# G1-CM4.net
KiCad netlist of a schematic drawn in Altium Designer
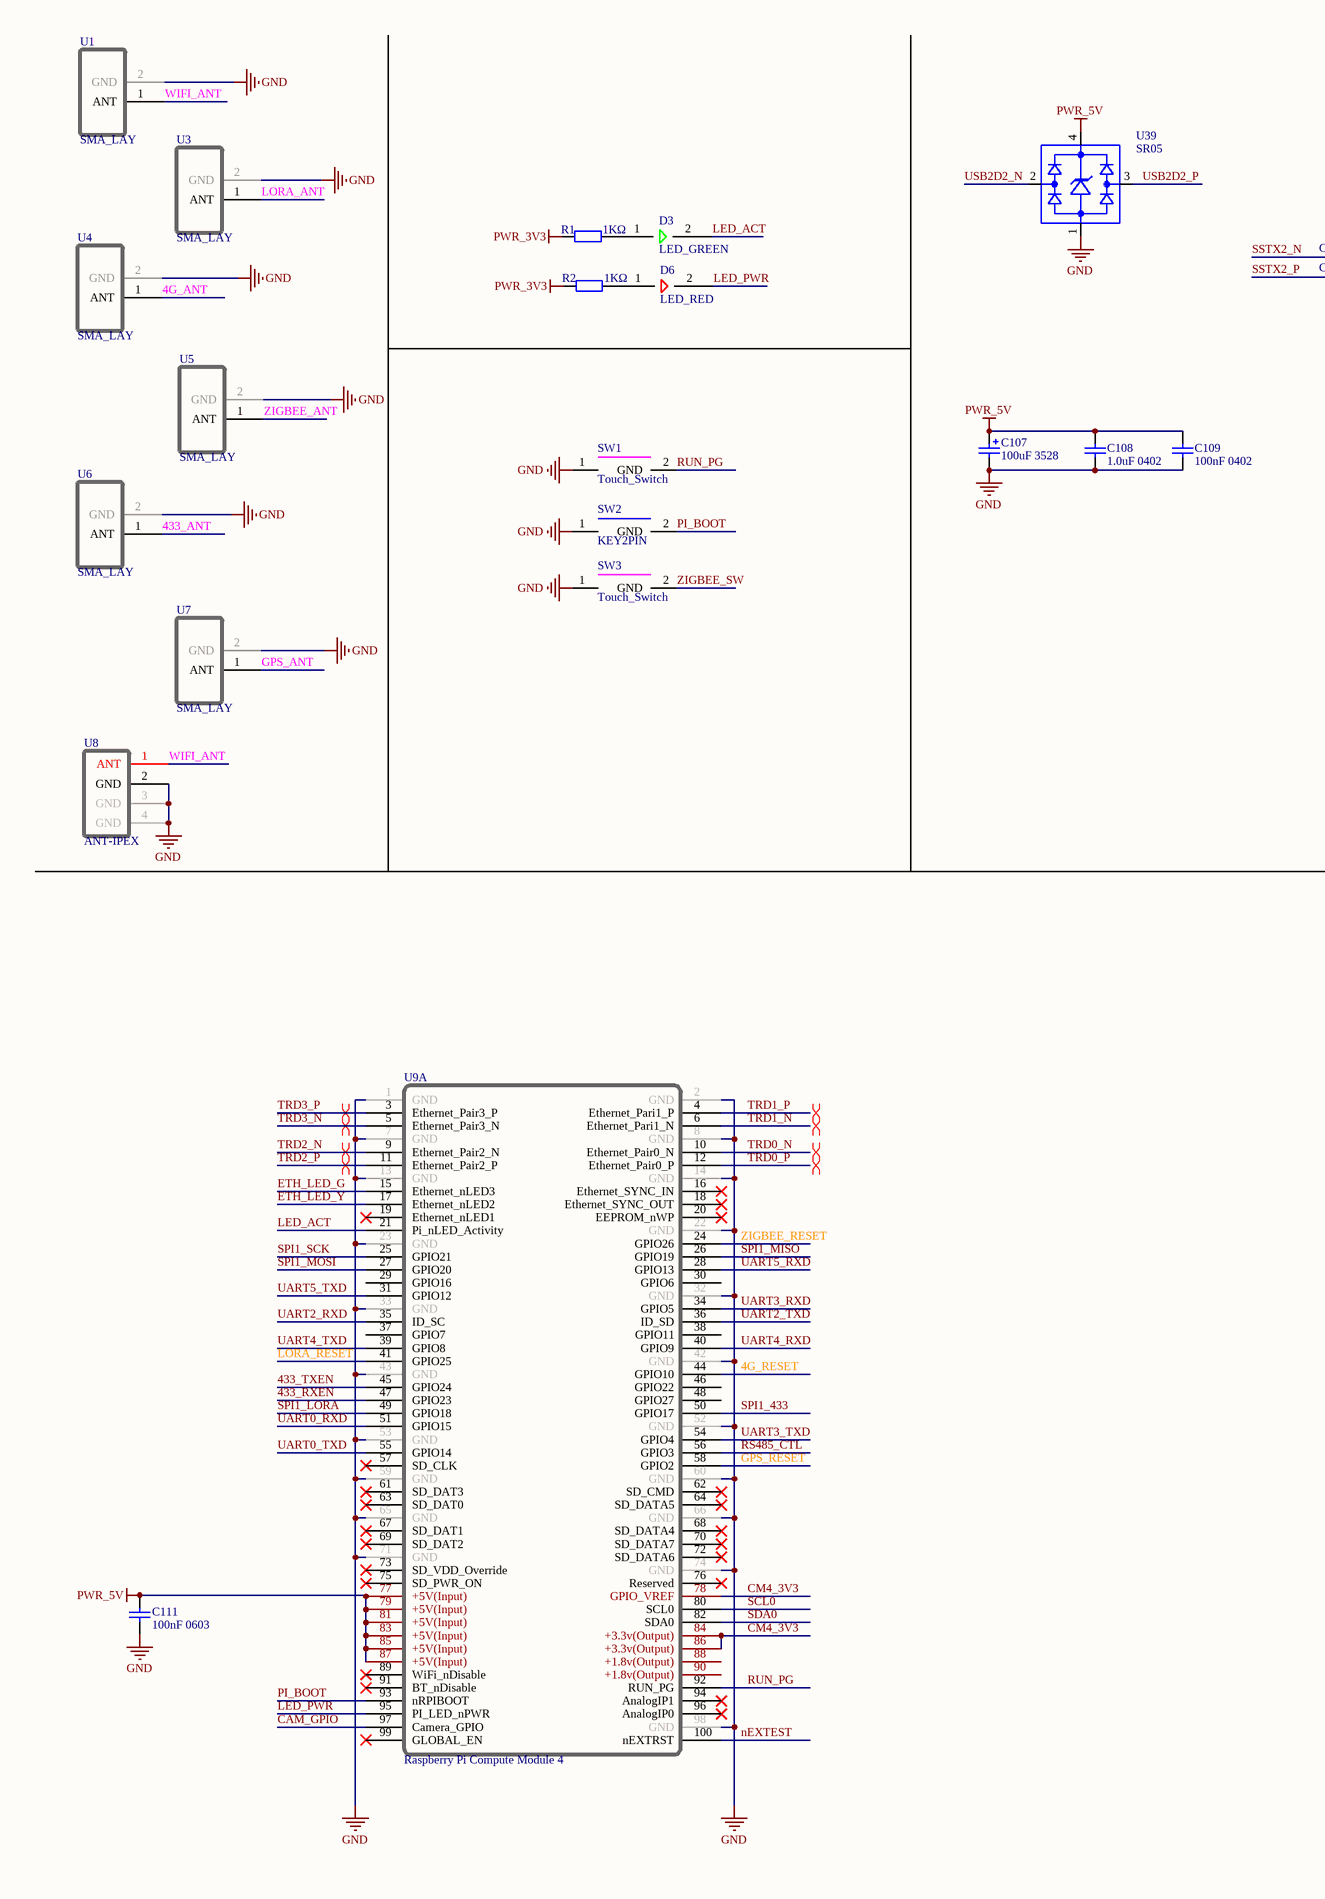
[diagram p0: G1-CM4.SchDoc, left]
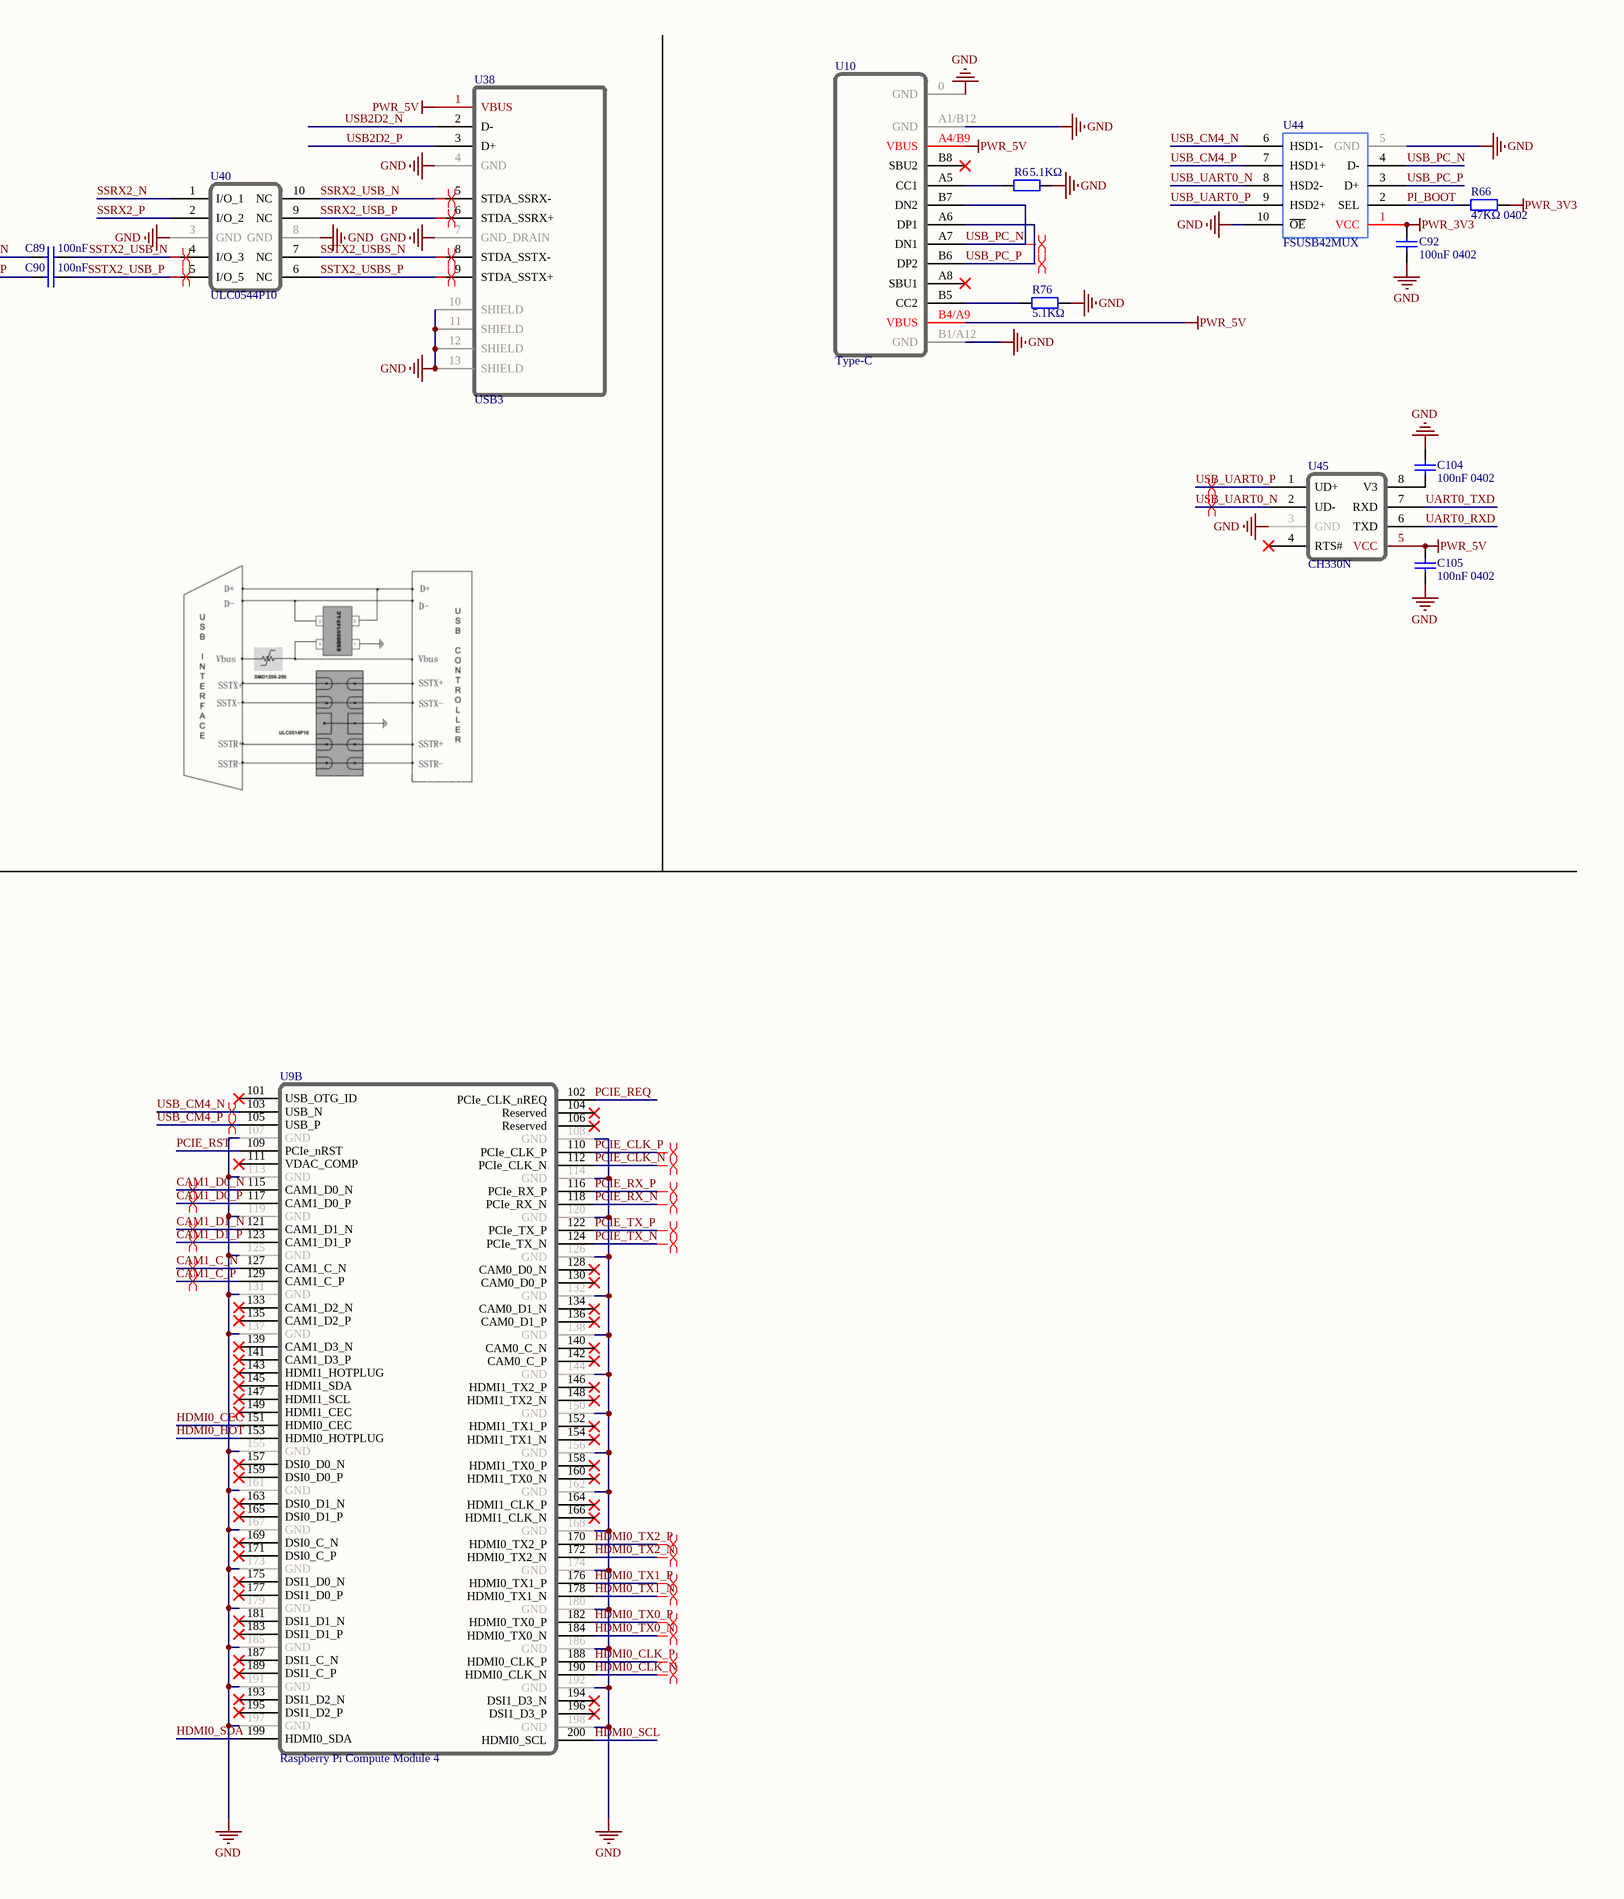
[diagram p1: G1-CM4.SchDoc, right]

(export (version "E")
  (design (tool "Eeschema 10.0.6"))
  (components
    (comp (ref "C89")
      (value "100nF")
      (footprint "0402_C")
      (description "贴片电容")
      (libsource (lib "Miscellaneous Devices LC") (part "0402 100nF (104) 10% 16V"))
    )
    (comp (ref "C90")
      (value "100nF")
      (footprint "0402_C")
      (description "贴片电容")
      (libsource (lib "Miscellaneous Devices LC") (part "0402 100nF (104) 10% 16V"))
    )
    (comp (ref "C92")
      (value "100nF 0402")
      (footprint "0402_C")
      (description "贴片电容")
      (libsource (lib "Miscellaneous Devices LC") (part "0402 100nF (104) 10% 16V"))
    )
    (comp (ref "C104")
      (value "100nF 0402")
      (footprint "0402_C")
      (description "贴片电容")
      (libsource (lib "Miscellaneous Devices LC") (part "0402 100nF (104) 10% 16V"))
    )
    (comp (ref "C105")
      (value "100nF 0402")
      (footprint "0402_C")
      (description "贴片电容")
      (libsource (lib "Miscellaneous Devices LC") (part "0402 100nF (104) 10% 16V"))
    )
    (comp (ref "C107")
      (value "100uF 3528")
      (footprint "CASE-B_3528")
      (description "钽电容")
      (libsource (lib "Miscellaneous Devices LC") (part "3528 100uF (107) 10% 6.3V"))
    )
    (comp (ref "C108")
      (value "1.0uF 0402")
      (footprint "0402_C")
      (description "贴片电容")
      (libsource (lib "Miscellaneous Devices LC") (part "0402 1.0uF (105) 10% 25V"))
    )
    (comp (ref "C109")
      (value "100nF 0402")
      (footprint "0402_C")
      (description "贴片电容")
      (libsource (lib "Miscellaneous Devices LC") (part "0402 100nF (104) 10% 16V"))
    )
    (comp (ref "C111")
      (value "100nF 0603")
      (footprint "0603_C")
      (description "贴片电容")
      (libsource (lib "Miscellaneous Devices LC") (part "0603 100nF (104) 10% 50V"))
    )
    (comp (ref "D3")
      (value "LED_GREEN")
      (footprint "LED_SIDE")
      (description "LED GREEN 0603 SIDE")
      (libsource (lib "bohao") (part "LED_GREEN"))
    )
    (comp (ref "D6")
      (value "LED_RED")
      (footprint "LED_SIDE")
      (description "LED RED 0603 SIDE")
      (libsource (lib "bohao") (part "LED_RED"))
    )
    (comp (ref "R1")
      (value "1KΩ")
      (footprint "0402_R")
      (description "贴片电阻")
      (libsource (lib "Miscellaneous Devices LC") (part "0402 1KΩ (1001) 1%"))
    )
    (comp (ref "R2")
      (value "1KΩ")
      (footprint "0402_R")
      (description "贴片电阻")
      (libsource (lib "Miscellaneous Devices LC") (part "0402 1KΩ (1001) 1%"))
    )
    (comp (ref "R6")
      (value "5.1KΩ")
      (footprint "0402_R")
      (description "贴片电阻")
      (libsource (lib "Miscellaneous Devices LC") (part "0402 5.1KΩ (5101) 1%"))
    )
    (comp (ref "R66")
      (value "47KΩ 0402")
      (footprint "0402_R")
      (description "贴片电阻")
      (libsource (lib "Miscellaneous Devices LC") (part "0402 47KΩ (4702) 1%"))
    )
    (comp (ref "R76")
      (value "5.1KΩ")
      (footprint "0402_R")
      (description "贴片电阻")
      (libsource (lib "Miscellaneous Devices LC") (part "0402 5.1KΩ (5101) 1%"))
    )
    (comp (ref "SW1")
      (value "Touch_Switch")
      (footprint "Touch_Switch")
      (description "Touch_Switch 2PIN")
      (libsource (lib "bohao") (part "Touch_Switch"))
    )
    (comp (ref "SW2")
      (value "KEY2PIN")
      (footprint "KEY2PIN")
      (description "Switch Button")
      (libsource (lib "bohao") (part "KEY2PIN"))
    )
    (comp (ref "SW3")
      (value "Touch_Switch")
      (footprint "Touch_Switch")
      (description "Touch_Switch 2PIN")
      (libsource (lib "bohao") (part "Touch_Switch"))
    )
    (comp (ref "U1")
      (value "SMA_LAY")
      (footprint "SMA-LAY")
      (description "SMA ANT LAY")
      (libsource (lib "bohao") (part "SMA_LAY"))
    )
    (comp (ref "U3")
      (value "SMA_LAY")
      (footprint "SMA-LAY")
      (description "SMA ANT LAY")
      (libsource (lib "bohao") (part "SMA_LAY"))
    )
    (comp (ref "U4")
      (value "SMA_LAY")
      (footprint "SMA-LAY")
      (description "SMA ANT LAY")
      (libsource (lib "bohao") (part "SMA_LAY"))
    )
    (comp (ref "U5")
      (value "SMA_LAY")
      (footprint "SMA-LAY")
      (description "SMA ANT LAY")
      (libsource (lib "bohao") (part "SMA_LAY"))
    )
    (comp (ref "U6")
      (value "SMA_LAY")
      (footprint "SMA-LAY")
      (description "SMA ANT LAY")
      (libsource (lib "bohao") (part "SMA_LAY"))
    )
    (comp (ref "U7")
      (value "SMA_LAY")
      (footprint "SMA-LAY")
      (description "SMA ANT LAY")
      (libsource (lib "bohao") (part "SMA_LAY"))
    )
    (comp (ref "U8")
      (value "ANT-IPEX")
      (footprint "ANT-IPEX")
      (description "ANT")
      (libsource (lib "bohao") (part "ANT-IPEX"))
    )
    (comp (ref "U9")
      (value "Raspberry Pi Compute Module 4")
      (footprint "CM4T-DF40HC(3.0)-100DS")
      (libsource (lib "bohao") (part "CM4"))
    )
    (comp (ref "U10")
      (value "Type-C")
      (footprint "Type-C-16P")
      (description "Type-C-16P")
      (libsource (lib "Mars") (part "Type-C-16P"))
    )
    (comp (ref "U38")
      (value "USB3")
      (footprint "USB3")
      (description "USB3.0")
      (libsource (lib "bohao") (part "USB3"))
    )
    (comp (ref "U39") (value "SR05") (footprint "SR05") (libsource (lib "bohao") (part "SR05")))
    (comp (ref "U40")
      (value "ULC0544P10")
      (footprint "ULC0544P10")
      (description "ESD")
      (libsource (lib "bohao") (part "ULC0544P10"))
    )
    (comp (ref "U44")
      (value "FSUSB42MUX")
      (footprint "FSUSB42MUX")
      (description "USB Switch IC 1 Channel, 10-Lead MSOP")
      (libsource (lib "bohao") (part "FSUSB42MUX"))
    )
    (comp (ref "U45")
      (value "CH330N")
      (footprint "CH330N")
      (description "USB to UART")
      (libsource (lib "bohao") (part "CH330N"))
    )
  )
  (nets
    (net (code "1") (name "/4G_ANT") (class "Default")
      (node (ref "U4") (pin "1") (pinfunction "ANT_1") (pintype "passive"))
    )
    (net (code "2") (name "/4G_RESET") (class "Default")
      (node (ref "U9") (pin "44") (pinfunction "GPIO10_44") (pintype "passive"))
    )
    (net (code "3") (name "/433_ANT") (class "Default")
      (node (ref "U6") (pin "1") (pinfunction "ANT_1") (pintype "passive"))
    )
    (net (code "4") (name "/433_RXEN") (class "Default")
      (node (ref "U9") (pin "47") (pinfunction "GPIO23_47") (pintype "passive"))
    )
    (net (code "5") (name "/433_TXEN") (class "Default")
      (node (ref "U9") (pin "45") (pinfunction "GPIO24_45") (pintype "passive"))
    )
    (net (code "6") (name "/CAM1_C_N") (class "Default")
      (node (ref "U9") (pin "127") (pinfunction "CAM1_C_N_127") (pintype "passive"))
    )
    (net (code "7") (name "/CAM1_C_P") (class "Default")
      (node (ref "U9") (pin "129") (pinfunction "CAM1_C_P_129") (pintype "passive"))
    )
    (net (code "8") (name "/CAM1_D0_N") (class "Default")
      (node (ref "U9") (pin "115") (pinfunction "CAM1_D0_N_115") (pintype "passive"))
    )
    (net (code "9") (name "/CAM1_D0_P") (class "Default")
      (node (ref "U9") (pin "117") (pinfunction "CAM1_D0_P_117") (pintype "passive"))
    )
    (net (code "10") (name "/CAM1_D1_N") (class "Default")
      (node (ref "U9") (pin "121") (pinfunction "CAM1_D1_N_121") (pintype "passive"))
    )
    (net (code "11") (name "/CAM1_D1_P") (class "Default")
      (node (ref "U9") (pin "123") (pinfunction "CAM1_D1_P_123") (pintype "passive"))
    )
    (net (code "12") (name "/CAM_GPIO") (class "Default")
      (node (ref "U9") (pin "97") (pinfunction "Camera_GPIO_97") (pintype "passive"))
    )
    (net (code "13") (name "/CM4_3V3") (class "Default")
      (node (ref "U9") (pin "78") (pinfunction "GPIO_VREF_78") (pintype "passive"))
      (node (ref "U9") (pin "84") (pinfunction "+3.3v(Output)_84") (pintype "passive"))
      (node (ref "U9") (pin "86") (pinfunction "+3.3v(Output)_86") (pintype "passive"))
    )
    (net (code "14") (name "/ETH_LED_G") (class "Default")
      (node (ref "U9") (pin "15") (pinfunction "Ethernet_nLED3_15") (pintype "passive"))
    )
    (net (code "15") (name "/ETH_LED_Y") (class "Default")
      (node (ref "U9") (pin "17") (pinfunction "Ethernet_nLED2_17") (pintype "passive"))
    )
    (net (code "16") (name "/GPS_ANT") (class "Default")
      (node (ref "U7") (pin "1") (pinfunction "ANT_1") (pintype "passive"))
    )
    (net (code "17") (name "/GPS_RESET") (class "Default")
      (node (ref "U9") (pin "58") (pinfunction "GPIO2_58") (pintype "passive"))
    )
    (net (code "18") (name "/HDMI0_CEC") (class "Default")
      (node (ref "U9") (pin "151") (pinfunction "HDMI0_CEC_151") (pintype "passive"))
    )
    (net (code "19") (name "/HDMI0_CLK_N") (class "Default")
      (node (ref "U9") (pin "190") (pinfunction "HDMI0_CLK_N_190") (pintype "passive"))
    )
    (net (code "20") (name "/HDMI0_CLK_P") (class "Default")
      (node (ref "U9") (pin "188") (pinfunction "HDMI0_CLK_P_188") (pintype "passive"))
    )
    (net (code "21") (name "/HDMI0_HOT") (class "Default")
      (node (ref "U9") (pin "153") (pinfunction "HDMI0_HOTPLUG_153") (pintype "passive"))
    )
    (net (code "22") (name "/HDMI0_SCL") (class "Default")
      (node (ref "U9") (pin "200") (pinfunction "HDMI0_SCL_200") (pintype "passive"))
    )
    (net (code "23") (name "/HDMI0_SDA") (class "Default")
      (node (ref "U9") (pin "199") (pinfunction "HDMI0_SDA_199") (pintype "passive"))
    )
    (net (code "24") (name "/HDMI0_TX0_N") (class "Default")
      (node (ref "U9") (pin "184") (pinfunction "HDMI0_TX0_N_184") (pintype "passive"))
    )
    (net (code "25") (name "/HDMI0_TX0_P") (class "Default")
      (node (ref "U9") (pin "182") (pinfunction "HDMI0_TX0_P_182") (pintype "passive"))
    )
    (net (code "26") (name "/HDMI0_TX1_N") (class "Default")
      (node (ref "U9") (pin "178") (pinfunction "HDMI0_TX1_N_178") (pintype "passive"))
    )
    (net (code "27") (name "/HDMI0_TX1_P") (class "Default")
      (node (ref "U9") (pin "176") (pinfunction "HDMI0_TX1_P_176") (pintype "passive"))
    )
    (net (code "28") (name "/HDMI0_TX2_N") (class "Default")
      (node (ref "U9") (pin "172") (pinfunction "HDMI0_TX2_N_172") (pintype "passive"))
    )
    (net (code "29") (name "/HDMI0_TX2_P") (class "Default")
      (node (ref "U9") (pin "170") (pinfunction "HDMI0_TX2_P_170") (pintype "passive"))
    )
    (net (code "30") (name "/LED_ACT") (class "Default")
      (node (ref "D3") (pin "2") (pintype "passive"))
      (node (ref "U9") (pin "21") (pinfunction "Pi_nLED_Activity_21") (pintype "passive"))
    )
    (net (code "31") (name "/LED_PWR") (class "Default")
      (node (ref "D6") (pin "2") (pintype "passive"))
      (node (ref "U9") (pin "95") (pinfunction "PI_LED_nPWR_95") (pintype "passive"))
    )
    (net (code "32") (name "/LORA_ANT") (class "Default")
      (node (ref "U3") (pin "1") (pinfunction "ANT_1") (pintype "passive"))
    )
    (net (code "33") (name "/LORA_RESET") (class "Default")
      (node (ref "U9") (pin "41") (pinfunction "GPIO25_41") (pintype "passive"))
    )
    (net (code "34") (name "/PCIE_CLK_N") (class "Default")
      (node (ref "U9") (pin "112") (pinfunction "PCIe_CLK_N_112") (pintype "passive"))
    )
    (net (code "35") (name "/PCIE_CLK_P") (class "Default")
      (node (ref "U9") (pin "110") (pinfunction "PCIe_CLK_P_110") (pintype "passive"))
    )
    (net (code "36") (name "/PCIE_REQ") (class "Default")
      (node (ref "U9") (pin "102") (pinfunction "PCIe_CLK_nREQ_102") (pintype "passive"))
    )
    (net (code "37") (name "/PCIE_RST") (class "Default")
      (node (ref "U9") (pin "109") (pinfunction "PCIe_nRST_109") (pintype "passive"))
    )
    (net (code "38") (name "/PCIE_RX_N") (class "Default")
      (node (ref "U9") (pin "118") (pinfunction "PCIe_RX_N_118") (pintype "passive"))
    )
    (net (code "39") (name "/PCIE_RX_P") (class "Default")
      (node (ref "U9") (pin "116") (pinfunction "PCIe_RX_P_116") (pintype "passive"))
    )
    (net (code "40") (name "/PCIE_TX_N") (class "Default")
      (node (ref "U9") (pin "124") (pinfunction "PCIe_TX_N_124") (pintype "passive"))
    )
    (net (code "41") (name "/PCIE_TX_P") (class "Default")
      (node (ref "U9") (pin "122") (pinfunction "PCIe_TX_P_122") (pintype "passive"))
    )
    (net (code "42") (name "/PI_BOOT") (class "Default")
      (node (ref "R66") (pin "2") (pinfunction "2_2") (pintype "passive"))
      (node (ref "SW2") (pin "2") (pinfunction "GND_2") (pintype "passive"))
      (node (ref "U44") (pin "2") (pinfunction "SEL_2") (pintype "passive"))
      (node (ref "U9") (pin "93") (pinfunction "nRPIBOOT_93") (pintype "passive"))
    )
    (net (code "43") (name "/RS485_CTL") (class "Default")
      (node (ref "U9") (pin "56") (pinfunction "GPIO3_56") (pintype "passive"))
    )
    (net (code "44") (name "/RUN_PG") (class "Default")
      (node (ref "SW1") (pin "2") (pinfunction "GND_2") (pintype "passive"))
      (node (ref "U9") (pin "92") (pinfunction "RUN_PG_92") (pintype "passive"))
    )
    (net (code "45") (name "/SCL0") (class "Default")
      (node (ref "U9") (pin "80") (pinfunction "SCL0_80") (pintype "passive"))
    )
    (net (code "46") (name "/SDA0") (class "Default")
      (node (ref "U9") (pin "82") (pinfunction "SDA0_82") (pintype "passive"))
    )
    (net (code "47") (name "/SPI1_433") (class "Default")
      (node (ref "U9") (pin "50") (pinfunction "GPIO17_50") (pintype "passive"))
    )
    (net (code "48") (name "/SPI1_LORA") (class "Default")
      (node (ref "U9") (pin "49") (pinfunction "GPIO18_49") (pintype "passive"))
    )
    (net (code "49") (name "/SPI1_MISO") (class "Default")
      (node (ref "U9") (pin "26") (pinfunction "GPIO19_26") (pintype "passive"))
    )
    (net (code "50") (name "/SPI1_MOSI") (class "Default")
      (node (ref "U9") (pin "27") (pinfunction "GPIO20_27") (pintype "passive"))
    )
    (net (code "51") (name "/SPI1_SCK") (class "Default")
      (node (ref "U9") (pin "25") (pinfunction "GPIO21_25") (pintype "passive"))
    )
    (net (code "52") (name "/SSRX2_N") (class "Default")
      (node (ref "U40") (pin "1") (pinfunction "I/O_1_1") (pintype "passive"))
    )
    (net (code "53") (name "/SSRX2_P") (class "Default")
      (node (ref "U40") (pin "2") (pinfunction "I/O_2_2") (pintype "passive"))
    )
    (net (code "54") (name "/SSRX2_USB_N") (class "Default")
      (node (ref "U38") (pin "5") (pinfunction "STDA_SSRX-_5") (pintype "passive"))
      (node (ref "U40") (pin "10") (pinfunction "NC_10") (pintype "passive"))
    )
    (net (code "55") (name "/SSRX2_USB_P") (class "Default")
      (node (ref "U38") (pin "6") (pinfunction "STDA_SSRX+_6") (pintype "passive"))
      (node (ref "U40") (pin "9") (pinfunction "NC_9") (pintype "passive"))
    )
    (net (code "56") (name "/SSTX2_N") (class "Default")
      (node (ref "C89") (pin "1") (pinfunction "1_1") (pintype "passive"))
    )
    (net (code "57") (name "/SSTX2_P") (class "Default")
      (node (ref "C90") (pin "1") (pinfunction "1_1") (pintype "passive"))
    )
    (net (code "58") (name "/SSTX2_USBS_N") (class "Default")
      (node (ref "U38") (pin "8") (pinfunction "STDA_SSTX-_8") (pintype "passive"))
      (node (ref "U40") (pin "7") (pinfunction "NC_7") (pintype "passive"))
    )
    (net (code "59") (name "/SSTX2_USBS_P") (class "Default")
      (node (ref "U38") (pin "9") (pinfunction "STDA_SSTX+_9") (pintype "passive"))
      (node (ref "U40") (pin "6") (pinfunction "NC_6") (pintype "passive"))
    )
    (net (code "60") (name "/SSTX2_USB_N") (class "Default")
      (node (ref "C89") (pin "2") (pinfunction "2_2") (pintype "passive"))
      (node (ref "U40") (pin "4") (pinfunction "I/O_3_4") (pintype "passive"))
    )
    (net (code "61") (name "/SSTX2_USB_P") (class "Default")
      (node (ref "C90") (pin "2") (pinfunction "2_2") (pintype "passive"))
      (node (ref "U40") (pin "5") (pinfunction "I/O_5_5") (pintype "passive"))
    )
    (net (code "62") (name "/TRD0_N") (class "Default")
      (node (ref "U9") (pin "10") (pinfunction "Ethernet_Pair0_N_10") (pintype "passive"))
    )
    (net (code "63") (name "/TRD0_P") (class "Default")
      (node (ref "U9") (pin "12") (pinfunction "Ethernet_Pair0_P_12") (pintype "passive"))
    )
    (net (code "64") (name "/TRD1_N") (class "Default")
      (node (ref "U9") (pin "6") (pinfunction "Ethernet_Pari1_N_6") (pintype "passive"))
    )
    (net (code "65") (name "/TRD1_P") (class "Default")
      (node (ref "U9") (pin "4") (pinfunction "Ethernet_Pari1_P_4") (pintype "passive"))
    )
    (net (code "66") (name "/TRD2_N") (class "Default")
      (node (ref "U9") (pin "9") (pinfunction "Ethernet_Pair2_N_9") (pintype "passive"))
    )
    (net (code "67") (name "/TRD2_P") (class "Default")
      (node (ref "U9") (pin "11") (pinfunction "Ethernet_Pair2_P_11") (pintype "passive"))
    )
    (net (code "68") (name "/TRD3_N") (class "Default")
      (node (ref "U9") (pin "5") (pinfunction "Ethernet_Pair3_N_5") (pintype "passive"))
    )
    (net (code "69") (name "/TRD3_P") (class "Default")
      (node (ref "U9") (pin "3") (pinfunction "Ethernet_Pair3_P_3") (pintype "passive"))
    )
    (net (code "70") (name "/UART0_RXD") (class "Default")
      (node (ref "U45") (pin "6") (pinfunction "TXD_6") (pintype "passive"))
      (node (ref "U9") (pin "51") (pinfunction "GPIO15_51") (pintype "passive"))
    )
    (net (code "71") (name "/UART0_TXD") (class "Default")
      (node (ref "U45") (pin "7") (pinfunction "RXD_7") (pintype "passive"))
      (node (ref "U9") (pin "55") (pinfunction "GPIO14_55") (pintype "passive"))
    )
    (net (code "72") (name "/UART2_RXD") (class "Default")
      (node (ref "U9") (pin "35") (pinfunction "ID_SC_35") (pintype "passive"))
    )
    (net (code "73") (name "/UART2_TXD") (class "Default")
      (node (ref "U9") (pin "36") (pinfunction "ID_SD_36") (pintype "passive"))
    )
    (net (code "74") (name "/UART3_RXD") (class "Default")
      (node (ref "U9") (pin "34") (pinfunction "GPIO5_34") (pintype "passive"))
    )
    (net (code "75") (name "/UART3_TXD") (class "Default")
      (node (ref "U9") (pin "54") (pinfunction "GPIO4_54") (pintype "passive"))
    )
    (net (code "76") (name "/UART4_RXD") (class "Default")
      (node (ref "U9") (pin "40") (pinfunction "GPIO9_40") (pintype "passive"))
    )
    (net (code "77") (name "/UART4_TXD") (class "Default")
      (node (ref "U9") (pin "39") (pinfunction "GPIO8_39") (pintype "passive"))
    )
    (net (code "78") (name "/UART5_RXD") (class "Default")
      (node (ref "U9") (pin "28") (pinfunction "GPIO13_28") (pintype "passive"))
    )
    (net (code "79") (name "/UART5_TXD") (class "Default")
      (node (ref "U9") (pin "31") (pinfunction "GPIO12_31") (pintype "passive"))
    )
    (net (code "80") (name "/USB2D2_N") (class "Default")
      (node (ref "U38") (pin "2") (pinfunction "D-_2") (pintype "passive"))
      (node (ref "U39") (pin "2") (pinfunction "2_2") (pintype "passive"))
    )
    (net (code "81") (name "/USB2D2_P") (class "Default")
      (node (ref "U38") (pin "3") (pinfunction "D+_3") (pintype "passive"))
      (node (ref "U39") (pin "3") (pinfunction "3_3") (pintype "passive"))
    )
    (net (code "82") (name "/USB_CM4_N") (class "Default")
      (node (ref "U44") (pin "6") (pinfunction "HSD1-_6") (pintype "passive"))
      (node (ref "U9") (pin "103") (pinfunction "USB_N_103") (pintype "passive"))
    )
    (net (code "83") (name "/USB_CM4_P") (class "Default")
      (node (ref "U44") (pin "7") (pinfunction "HSD1+_7") (pintype "passive"))
      (node (ref "U9") (pin "105") (pinfunction "USB_P_105") (pintype "passive"))
    )
    (net (code "84") (name "/USB_PC_N") (class "Default")
      (node (ref "U10") (pin "A7") (pinfunction "DN1_A7") (pintype "passive"))
      (node (ref "U10") (pin "B7") (pinfunction "DN2_B7") (pintype "passive"))
      (node (ref "U44") (pin "4") (pinfunction "D-_4") (pintype "passive"))
    )
    (net (code "85") (name "/USB_PC_P") (class "Default")
      (node (ref "U10") (pin "A6") (pinfunction "DP1_A6") (pintype "passive"))
      (node (ref "U10") (pin "B6") (pinfunction "DP2_B6") (pintype "passive"))
      (node (ref "U44") (pin "3") (pinfunction "D+_3") (pintype "passive"))
    )
    (net (code "86") (name "/USB_UART0_N") (class "Default")
      (node (ref "U44") (pin "8") (pinfunction "HSD2-_8") (pintype "passive"))
      (node (ref "U45") (pin "2") (pinfunction "UD-_2") (pintype "passive"))
    )
    (net (code "87") (name "/USB_UART0_P") (class "Default")
      (node (ref "U44") (pin "9") (pinfunction "HSD2+_9") (pintype "passive"))
      (node (ref "U45") (pin "1") (pinfunction "UD+_1") (pintype "passive"))
    )
    (net (code "88") (name "/WIFI_ANT") (class "Default")
      (node (ref "U1") (pin "1") (pinfunction "ANT_1") (pintype "passive"))
      (node (ref "U8") (pin "1") (pinfunction "ANT_1") (pintype "passive"))
    )
    (net (code "89") (name "/ZIGBEE_ANT") (class "Default")
      (node (ref "U5") (pin "1") (pinfunction "ANT_1") (pintype "passive"))
    )
    (net (code "90") (name "/ZIGBEE_RESET") (class "Default")
      (node (ref "U9") (pin "24") (pinfunction "GPIO26_24") (pintype "passive"))
    )
    (net (code "91") (name "/ZIGBEE_SW") (class "Default")
      (node (ref "SW3") (pin "2") (pinfunction "GND_2") (pintype "passive"))
    )
    (net (code "92") (name "/nEXTEST") (class "Default")
      (node (ref "U9") (pin "100") (pinfunction "nEXTRST_100") (pintype "passive"))
    )
    (net (code "93") (name "GND") (class "Default")
      (node (ref "C104") (pin "2") (pinfunction "2_2") (pintype "passive"))
      (node (ref "C105") (pin "1") (pinfunction "1_1") (pintype "passive"))
      (node (ref "C107") (pin "2") (pinfunction "2_2") (pintype "passive"))
      (node (ref "C108") (pin "1") (pinfunction "1_1") (pintype "passive"))
      (node (ref "C109") (pin "1") (pinfunction "1_1") (pintype "passive"))
      (node (ref "C111") (pin "1") (pinfunction "1_1") (pintype "passive"))
      (node (ref "C92") (pin "1") (pinfunction "1_1") (pintype "passive"))
      (node (ref "R6") (pin "2") (pinfunction "2_2") (pintype "passive"))
      (node (ref "R76") (pin "2") (pinfunction "2_2") (pintype "passive"))
      (node (ref "SW1") (pin "1") (pinfunction "1_1") (pintype "passive"))
      (node (ref "SW2") (pin "1") (pinfunction "1_1") (pintype "passive"))
      (node (ref "SW3") (pin "1") (pinfunction "1_1") (pintype "passive"))
      (node (ref "U1") (pin "2") (pinfunction "GND_2") (pintype "passive"))
      (node (ref "U10") (pin "0") (pinfunction "GND_0") (pintype "passive"))
      (node (ref "U10") (pin "A1/B12") (pinfunction "GND_A1/B12") (pintype "passive"))
      (node (ref "U10") (pin "B1/A12") (pinfunction "GND_B1/A12") (pintype "passive"))
      (node (ref "U3") (pin "2") (pinfunction "GND_2") (pintype "passive"))
      (node (ref "U38") (pin "10") (pinfunction "SHIELD_10") (pintype "passive"))
      (node (ref "U38") (pin "11") (pinfunction "SHIELD_11") (pintype "passive"))
      (node (ref "U38") (pin "12") (pinfunction "SHIELD_12") (pintype "passive"))
      (node (ref "U38") (pin "13") (pinfunction "SHIELD_13") (pintype "passive"))
      (node (ref "U38") (pin "4") (pinfunction "GND_4") (pintype "passive"))
      (node (ref "U38") (pin "7") (pinfunction "GND_DRAIN_7") (pintype "passive"))
      (node (ref "U39") (pin "1") (pinfunction "1_1") (pintype "passive"))
      (node (ref "U4") (pin "2") (pinfunction "GND_2") (pintype "passive"))
      (node (ref "U40") (pin "3") (pinfunction "GND_3") (pintype "passive"))
      (node (ref "U40") (pin "8") (pinfunction "GND_8") (pintype "passive"))
      (node (ref "U44") (pin "10") (pinfunction "~{OE}_10") (pintype "passive"))
      (node (ref "U44") (pin "5") (pinfunction "GND_5") (pintype "passive"))
      (node (ref "U45") (pin "3") (pinfunction "GND_3") (pintype "passive"))
      (node (ref "U5") (pin "2") (pinfunction "GND_2") (pintype "passive"))
      (node (ref "U6") (pin "2") (pinfunction "GND_2") (pintype "passive"))
      (node (ref "U7") (pin "2") (pinfunction "GND_2") (pintype "passive"))
      (node (ref "U8") (pin "2") (pinfunction "GND_2") (pintype "passive"))
      (node (ref "U8") (pin "3") (pinfunction "GND_3") (pintype "passive"))
      (node (ref "U8") (pin "4") (pinfunction "GND_4") (pintype "passive"))
      (node (ref "U9") (pin "1") (pinfunction "GND_1") (pintype "passive"))
      (node (ref "U9") (pin "107") (pinfunction "GND_107") (pintype "passive"))
      (node (ref "U9") (pin "108") (pinfunction "GND_108") (pintype "passive"))
      (node (ref "U9") (pin "113") (pinfunction "GND_113") (pintype "passive"))
      (node (ref "U9") (pin "114") (pinfunction "GND_114") (pintype "passive"))
      (node (ref "U9") (pin "119") (pinfunction "GND_119") (pintype "passive"))
      (node (ref "U9") (pin "120") (pinfunction "GND_120") (pintype "passive"))
      (node (ref "U9") (pin "125") (pinfunction "GND_125") (pintype "passive"))
      (node (ref "U9") (pin "126") (pinfunction "GND_126") (pintype "passive"))
      (node (ref "U9") (pin "13") (pinfunction "GND_13") (pintype "passive"))
      (node (ref "U9") (pin "131") (pinfunction "GND_131") (pintype "passive"))
      (node (ref "U9") (pin "132") (pinfunction "GND_132") (pintype "passive"))
      (node (ref "U9") (pin "137") (pinfunction "GND_137") (pintype "passive"))
      (node (ref "U9") (pin "138") (pinfunction "GND_138") (pintype "passive"))
      (node (ref "U9") (pin "14") (pinfunction "GND_14") (pintype "passive"))
      (node (ref "U9") (pin "144") (pinfunction "GND_144") (pintype "passive"))
      (node (ref "U9") (pin "150") (pinfunction "GND_150") (pintype "passive"))
      (node (ref "U9") (pin "155") (pinfunction "GND_155") (pintype "passive"))
      (node (ref "U9") (pin "156") (pinfunction "GND_156") (pintype "passive"))
      (node (ref "U9") (pin "161") (pinfunction "GND_161") (pintype "passive"))
      (node (ref "U9") (pin "162") (pinfunction "GND_162") (pintype "passive"))
      (node (ref "U9") (pin "167") (pinfunction "GND_167") (pintype "passive"))
      (node (ref "U9") (pin "168") (pinfunction "GND_168") (pintype "passive"))
      (node (ref "U9") (pin "173") (pinfunction "GND_173") (pintype "passive"))
      (node (ref "U9") (pin "174") (pinfunction "GND_174") (pintype "passive"))
      (node (ref "U9") (pin "179") (pinfunction "GND_179") (pintype "passive"))
      (node (ref "U9") (pin "180") (pinfunction "GND_180") (pintype "passive"))
      (node (ref "U9") (pin "185") (pinfunction "GND_185") (pintype "passive"))
      (node (ref "U9") (pin "186") (pinfunction "GND_186") (pintype "passive"))
      (node (ref "U9") (pin "191") (pinfunction "GND_191") (pintype "passive"))
      (node (ref "U9") (pin "192") (pinfunction "GND_192") (pintype "passive"))
      (node (ref "U9") (pin "197") (pinfunction "GND_197") (pintype "passive"))
      (node (ref "U9") (pin "198") (pinfunction "GND_198") (pintype "passive"))
      (node (ref "U9") (pin "2") (pinfunction "GND_2") (pintype "passive"))
      (node (ref "U9") (pin "22") (pinfunction "GND_22") (pintype "passive"))
      (node (ref "U9") (pin "23") (pinfunction "GND_23") (pintype "passive"))
      (node (ref "U9") (pin "32") (pinfunction "GND_32") (pintype "passive"))
      (node (ref "U9") (pin "33") (pinfunction "GND_33") (pintype "passive"))
      (node (ref "U9") (pin "42") (pinfunction "GND_42") (pintype "passive"))
      (node (ref "U9") (pin "43") (pinfunction "GND_43") (pintype "passive"))
      (node (ref "U9") (pin "52") (pinfunction "GND_52") (pintype "passive"))
      (node (ref "U9") (pin "53") (pinfunction "GND_53") (pintype "passive"))
      (node (ref "U9") (pin "59") (pinfunction "GND_59") (pintype "passive"))
      (node (ref "U9") (pin "60") (pinfunction "GND_60") (pintype "passive"))
      (node (ref "U9") (pin "65") (pinfunction "GND_65") (pintype "passive"))
      (node (ref "U9") (pin "66") (pinfunction "GND_66") (pintype "passive"))
      (node (ref "U9") (pin "7") (pinfunction "GND_7") (pintype "passive"))
      (node (ref "U9") (pin "71") (pinfunction "GND_71") (pintype "passive"))
      (node (ref "U9") (pin "74") (pinfunction "GND_74") (pintype "passive"))
      (node (ref "U9") (pin "8") (pinfunction "GND_8") (pintype "passive"))
      (node (ref "U9") (pin "98") (pinfunction "GND_98") (pintype "passive"))
    )
    (net (code "94") (name "Net-(D3-Pad1)") (class "Default")
      (node (ref "D3") (pin "1") (pintype "passive"))
      (node (ref "R1") (pin "2") (pinfunction "2_2") (pintype "passive"))
    )
    (net (code "95") (name "Net-(D6-Pad1)") (class "Default")
      (node (ref "D6") (pin "1") (pintype "passive"))
      (node (ref "R2") (pin "2") (pinfunction "2_2") (pintype "passive"))
    )
    (net (code "96") (name "Net-(U10-CC1)") (class "Default")
      (node (ref "R6") (pin "1") (pinfunction "1_1") (pintype "passive"))
      (node (ref "U10") (pin "A5") (pinfunction "CC1_A5") (pintype "passive"))
    )
    (net (code "97") (name "Net-(U10-CC2)") (class "Default")
      (node (ref "R76") (pin "1") (pinfunction "1_1") (pintype "passive"))
      (node (ref "U10") (pin "B5") (pinfunction "CC2_B5") (pintype "passive"))
    )
    (net (code "98") (name "Net-(U45-V3)") (class "Default")
      (node (ref "C104") (pin "1") (pinfunction "1_1") (pintype "passive"))
      (node (ref "U45") (pin "8") (pinfunction "V3_8") (pintype "passive"))
    )
    (net (code "99") (name "PWR_3V3") (class "Default")
      (node (ref "C92") (pin "2") (pinfunction "2_2") (pintype "passive"))
      (node (ref "R1") (pin "1") (pinfunction "1_1") (pintype "passive"))
      (node (ref "R2") (pin "1") (pinfunction "1_1") (pintype "passive"))
      (node (ref "R66") (pin "1") (pinfunction "1_1") (pintype "passive"))
      (node (ref "U44") (pin "1") (pinfunction "VCC_1") (pintype "passive"))
    )
    (net (code "100") (name "PWR_5V") (class "Default")
      (node (ref "C105") (pin "2") (pinfunction "2_2") (pintype "passive"))
      (node (ref "C107") (pin "1") (pinfunction "1_1") (pintype "passive"))
      (node (ref "C108") (pin "2") (pinfunction "2_2") (pintype "passive"))
      (node (ref "C109") (pin "2") (pinfunction "2_2") (pintype "passive"))
      (node (ref "C111") (pin "2") (pinfunction "2_2") (pintype "passive"))
      (node (ref "U10") (pin "A4/B9") (pinfunction "VBUS_A4/B9") (pintype "passive"))
      (node (ref "U10") (pin "B4/A9") (pinfunction "VBUS_B4/A9") (pintype "passive"))
      (node (ref "U38") (pin "1") (pinfunction "VBUS_1") (pintype "power_in"))
      (node (ref "U39") (pin "4") (pinfunction "4_4") (pintype "passive"))
      (node (ref "U45") (pin "5") (pinfunction "VCC_5") (pintype "passive"))
      (node (ref "U9") (pin "77") (pinfunction "+5V(Input)_77") (pintype "passive"))
      (node (ref "U9") (pin "79") (pinfunction "+5V(Input)_79") (pintype "passive"))
      (node (ref "U9") (pin "81") (pinfunction "+5V(Input)_81") (pintype "passive"))
      (node (ref "U9") (pin "83") (pinfunction "+5V(Input)_83") (pintype "passive"))
      (node (ref "U9") (pin "85") (pinfunction "+5V(Input)_85") (pintype "passive"))
      (node (ref "U9") (pin "87") (pinfunction "+5V(Input)_87") (pintype "passive"))
    )
    (net (code "101") (name "unconnected-(U9A-+1.8v(Output)-Pad88)") (class "Default")
      (node (ref "U9") (pin "88") (pinfunction "+1.8v(Output)_88") (pintype "passive"))
    )
    (net (code "102") (name "unconnected-(U9A-+1.8v(Output)-Pad90)") (class "Default")
      (node (ref "U9") (pin "90") (pinfunction "+1.8v(Output)_90") (pintype "passive"))
    )
    (net (code "103") (name "unconnected-(U9A-AnalogIP0-Pad96)") (class "Default")
      (node (ref "U9") (pin "96") (pinfunction "AnalogIP0_96") (pintype "passive+no_connect"))
    )
    (net (code "104") (name "unconnected-(U9A-AnalogIP1-Pad94)") (class "Default")
      (node (ref "U9") (pin "94") (pinfunction "AnalogIP1_94") (pintype "passive+no_connect"))
    )
    (net (code "105") (name "unconnected-(U9A-BT_nDisable-Pad91)") (class "Default")
      (node (ref "U9") (pin "91") (pinfunction "BT_nDisable_91") (pintype "passive+no_connect"))
    )
    (net (code "106") (name "unconnected-(U9A-EEPROM_nWP-Pad20)") (class "Default")
      (node (ref "U9") (pin "20") (pinfunction "EEPROM_nWP_20") (pintype "passive+no_connect"))
    )
    (net (code "107") (name "unconnected-(U9A-Ethernet_SYNC_IN-Pad16)") (class "Default")
      (node (ref "U9") (pin "16") (pinfunction "Ethernet_SYNC_IN_16") (pintype "passive+no_connect"))
    )
    (net (code "108") (name "unconnected-(U9A-Ethernet_SYNC_OUT-Pad18)") (class "Default")
      (node (ref "U9") (pin "18") (pinfunction "Ethernet_SYNC_OUT_18") (pintype "passive+no_connect"))
    )
    (net (code "109") (name "unconnected-(U9A-Ethernet_nLED1-Pad19)") (class "Default")
      (node (ref "U9") (pin "19") (pinfunction "Ethernet_nLED1_19") (pintype "passive+no_connect"))
    )
    (net (code "110") (name "unconnected-(U9A-GLOBAL_EN-Pad99)") (class "Default")
      (node (ref "U9") (pin "99") (pinfunction "GLOBAL_EN_99") (pintype "passive+no_connect"))
    )
    (net (code "111") (name "unconnected-(U9A-GPIO6-Pad30)") (class "Default")
      (node (ref "U9") (pin "30") (pinfunction "GPIO6_30") (pintype "passive"))
    )
    (net (code "112") (name "unconnected-(U9A-GPIO7-Pad37)") (class "Default")
      (node (ref "U9") (pin "37") (pinfunction "GPIO7_37") (pintype "passive"))
    )
    (net (code "113") (name "unconnected-(U9A-GPIO11-Pad38)") (class "Default")
      (node (ref "U9") (pin "38") (pinfunction "GPIO11_38") (pintype "passive"))
    )
    (net (code "114") (name "unconnected-(U9A-GPIO16-Pad29)") (class "Default")
      (node (ref "U9") (pin "29") (pinfunction "GPIO16_29") (pintype "passive"))
    )
    (net (code "115") (name "unconnected-(U9A-GPIO22-Pad46)") (class "Default")
      (node (ref "U9") (pin "46") (pinfunction "GPIO22_46") (pintype "passive"))
    )
    (net (code "116") (name "unconnected-(U9A-GPIO27-Pad48)") (class "Default")
      (node (ref "U9") (pin "48") (pinfunction "GPIO27_48") (pintype "passive"))
    )
    (net (code "117") (name "unconnected-(U9A-Reserved-Pad76)") (class "Default")
      (node (ref "U9") (pin "76") (pinfunction "Reserved_76") (pintype "passive+no_connect"))
    )
    (net (code "118") (name "unconnected-(U9A-SD_CLK-Pad57)") (class "Default")
      (node (ref "U9") (pin "57") (pinfunction "SD_CLK_57") (pintype "passive+no_connect"))
    )
    (net (code "119") (name "unconnected-(U9A-SD_CMD-Pad62)") (class "Default")
      (node (ref "U9") (pin "62") (pinfunction "SD_CMD_62") (pintype "passive+no_connect"))
    )
    (net (code "120") (name "unconnected-(U9A-SD_DAT0-Pad63)") (class "Default")
      (node (ref "U9") (pin "63") (pinfunction "SD_DAT0_63") (pintype "passive+no_connect"))
    )
    (net (code "121") (name "unconnected-(U9A-SD_DAT1-Pad67)") (class "Default")
      (node (ref "U9") (pin "67") (pinfunction "SD_DAT1_67") (pintype "passive+no_connect"))
    )
    (net (code "122") (name "unconnected-(U9A-SD_DAT2-Pad69)") (class "Default")
      (node (ref "U9") (pin "69") (pinfunction "SD_DAT2_69") (pintype "passive+no_connect"))
    )
    (net (code "123") (name "unconnected-(U9A-SD_DAT3-Pad61)") (class "Default")
      (node (ref "U9") (pin "61") (pinfunction "SD_DAT3_61") (pintype "passive+no_connect"))
    )
    (net (code "124") (name "unconnected-(U9A-SD_DATA4-Pad68)") (class "Default")
      (node (ref "U9") (pin "68") (pinfunction "SD_DATA4_68") (pintype "passive+no_connect"))
    )
    (net (code "125") (name "unconnected-(U9A-SD_DATA5-Pad64)") (class "Default")
      (node (ref "U9") (pin "64") (pinfunction "SD_DATA5_64") (pintype "passive+no_connect"))
    )
    (net (code "126") (name "unconnected-(U9A-SD_DATA6-Pad72)") (class "Default")
      (node (ref "U9") (pin "72") (pinfunction "SD_DATA6_72") (pintype "passive+no_connect"))
    )
    (net (code "127") (name "unconnected-(U9A-SD_DATA7-Pad70)") (class "Default")
      (node (ref "U9") (pin "70") (pinfunction "SD_DATA7_70") (pintype "passive+no_connect"))
    )
    (net (code "128") (name "unconnected-(U9A-SD_PWR_ON-Pad75)") (class "Default")
      (node (ref "U9") (pin "75") (pinfunction "SD_PWR_ON_75") (pintype "passive+no_connect"))
    )
    (net (code "129") (name "unconnected-(U9A-SD_VDD_Override-Pad73)") (class "Default")
      (node (ref "U9") (pin "73") (pinfunction "SD_VDD_Override_73") (pintype "passive+no_connect"))
    )
    (net (code "130") (name "unconnected-(U9A-WiFi_nDisable-Pad89)") (class "Default")
      (node (ref "U9") (pin "89") (pinfunction "WiFi_nDisable_89") (pintype "passive+no_connect"))
    )
    (net (code "131") (name "unconnected-(U9B-CAM0_C_N-Pad140)") (class "Default")
      (node (ref "U9") (pin "140") (pinfunction "CAM0_C_N_140") (pintype "passive+no_connect"))
    )
    (net (code "132") (name "unconnected-(U9B-CAM0_C_P-Pad142)") (class "Default")
      (node (ref "U9") (pin "142") (pinfunction "CAM0_C_P_142") (pintype "passive+no_connect"))
    )
    (net (code "133") (name "unconnected-(U9B-CAM0_D0_N-Pad128)") (class "Default")
      (node (ref "U9") (pin "128") (pinfunction "CAM0_D0_N_128") (pintype "passive+no_connect"))
    )
    (net (code "134") (name "unconnected-(U9B-CAM0_D0_P-Pad130)") (class "Default")
      (node (ref "U9") (pin "130") (pinfunction "CAM0_D0_P_130") (pintype "passive+no_connect"))
    )
    (net (code "135") (name "unconnected-(U9B-CAM0_D1_N-Pad134)") (class "Default")
      (node (ref "U9") (pin "134") (pinfunction "CAM0_D1_N_134") (pintype "passive+no_connect"))
    )
    (net (code "136") (name "unconnected-(U9B-CAM0_D1_P-Pad136)") (class "Default")
      (node (ref "U9") (pin "136") (pinfunction "CAM0_D1_P_136") (pintype "passive+no_connect"))
    )
    (net (code "137") (name "unconnected-(U9B-CAM1_D2_N-Pad133)") (class "Default")
      (node (ref "U9") (pin "133") (pinfunction "CAM1_D2_N_133") (pintype "passive+no_connect"))
    )
    (net (code "138") (name "unconnected-(U9B-CAM1_D2_P-Pad135)") (class "Default")
      (node (ref "U9") (pin "135") (pinfunction "CAM1_D2_P_135") (pintype "passive+no_connect"))
    )
    (net (code "139") (name "unconnected-(U9B-CAM1_D3_N-Pad139)") (class "Default")
      (node (ref "U9") (pin "139") (pinfunction "CAM1_D3_N_139") (pintype "passive+no_connect"))
    )
    (net (code "140") (name "unconnected-(U9B-CAM1_D3_P-Pad141)") (class "Default")
      (node (ref "U9") (pin "141") (pinfunction "CAM1_D3_P_141") (pintype "passive+no_connect"))
    )
    (net (code "141") (name "unconnected-(U9B-DSI0_C_N-Pad169)") (class "Default")
      (node (ref "U9") (pin "169") (pinfunction "DSI0_C_N_169") (pintype "passive+no_connect"))
    )
    (net (code "142") (name "unconnected-(U9B-DSI0_C_P-Pad171)") (class "Default")
      (node (ref "U9") (pin "171") (pinfunction "DSI0_C_P_171") (pintype "passive+no_connect"))
    )
    (net (code "143") (name "unconnected-(U9B-DSI0_D0_N-Pad157)") (class "Default")
      (node (ref "U9") (pin "157") (pinfunction "DSI0_D0_N_157") (pintype "passive+no_connect"))
    )
    (net (code "144") (name "unconnected-(U9B-DSI0_D0_P-Pad159)") (class "Default")
      (node (ref "U9") (pin "159") (pinfunction "DSI0_D0_P_159") (pintype "passive+no_connect"))
    )
    (net (code "145") (name "unconnected-(U9B-DSI0_D1_N-Pad163)") (class "Default")
      (node (ref "U9") (pin "163") (pinfunction "DSI0_D1_N_163") (pintype "passive+no_connect"))
    )
    (net (code "146") (name "unconnected-(U9B-DSI0_D1_P-Pad165)") (class "Default")
      (node (ref "U9") (pin "165") (pinfunction "DSI0_D1_P_165") (pintype "passive+no_connect"))
    )
    (net (code "147") (name "unconnected-(U9B-DSI1_C_N-Pad187)") (class "Default")
      (node (ref "U9") (pin "187") (pinfunction "DSI1_C_N_187") (pintype "passive+no_connect"))
    )
    (net (code "148") (name "unconnected-(U9B-DSI1_C_P-Pad189)") (class "Default")
      (node (ref "U9") (pin "189") (pinfunction "DSI1_C_P_189") (pintype "passive+no_connect"))
    )
    (net (code "149") (name "unconnected-(U9B-DSI1_D0_N-Pad175)") (class "Default")
      (node (ref "U9") (pin "175") (pinfunction "DSI1_D0_N_175") (pintype "passive+no_connect"))
    )
    (net (code "150") (name "unconnected-(U9B-DSI1_D0_P-Pad177)") (class "Default")
      (node (ref "U9") (pin "177") (pinfunction "DSI1_D0_P_177") (pintype "passive+no_connect"))
    )
    (net (code "151") (name "unconnected-(U9B-DSI1_D1_N-Pad181)") (class "Default")
      (node (ref "U9") (pin "181") (pinfunction "DSI1_D1_N_181") (pintype "passive+no_connect"))
    )
    (net (code "152") (name "unconnected-(U9B-DSI1_D1_P-Pad183)") (class "Default")
      (node (ref "U9") (pin "183") (pinfunction "DSI1_D1_P_183") (pintype "passive+no_connect"))
    )
    (net (code "153") (name "unconnected-(U9B-DSI1_D2_N-Pad193)") (class "Default")
      (node (ref "U9") (pin "193") (pinfunction "DSI1_D2_N_193") (pintype "passive+no_connect"))
    )
    (net (code "154") (name "unconnected-(U9B-DSI1_D2_P-Pad195)") (class "Default")
      (node (ref "U9") (pin "195") (pinfunction "DSI1_D2_P_195") (pintype "passive+no_connect"))
    )
    (net (code "155") (name "unconnected-(U9B-DSI1_D3_N-Pad194)") (class "Default")
      (node (ref "U9") (pin "194") (pinfunction "DSI1_D3_N_194") (pintype "passive+no_connect"))
    )
    (net (code "156") (name "unconnected-(U9B-DSI1_D3_P-Pad196)") (class "Default")
      (node (ref "U9") (pin "196") (pinfunction "DSI1_D3_P_196") (pintype "passive+no_connect"))
    )
    (net (code "157") (name "unconnected-(U9B-HDMI1_CEC-Pad149)") (class "Default")
      (node (ref "U9") (pin "149") (pinfunction "HDMI1_CEC_149") (pintype "passive+no_connect"))
    )
    (net (code "158") (name "unconnected-(U9B-HDMI1_CLK_N-Pad166)") (class "Default")
      (node (ref "U9") (pin "166") (pinfunction "HDMI1_CLK_N_166") (pintype "passive+no_connect"))
    )
    (net (code "159") (name "unconnected-(U9B-HDMI1_CLK_P-Pad164)") (class "Default")
      (node (ref "U9") (pin "164") (pinfunction "HDMI1_CLK_P_164") (pintype "passive+no_connect"))
    )
    (net (code "160") (name "unconnected-(U9B-HDMI1_HOTPLUG-Pad143)") (class "Default")
      (node (ref "U9") (pin "143") (pinfunction "HDMI1_HOTPLUG_143") (pintype "passive+no_connect"))
    )
    (net (code "161") (name "unconnected-(U9B-HDMI1_SCL-Pad147)") (class "Default")
      (node (ref "U9") (pin "147") (pinfunction "HDMI1_SCL_147") (pintype "passive+no_connect"))
    )
    (net (code "162") (name "unconnected-(U9B-HDMI1_SDA-Pad145)") (class "Default")
      (node (ref "U9") (pin "145") (pinfunction "HDMI1_SDA_145") (pintype "passive+no_connect"))
    )
    (net (code "163") (name "unconnected-(U9B-HDMI1_TX0_N-Pad160)") (class "Default")
      (node (ref "U9") (pin "160") (pinfunction "HDMI1_TX0_N_160") (pintype "passive+no_connect"))
    )
    (net (code "164") (name "unconnected-(U9B-HDMI1_TX0_P-Pad158)") (class "Default")
      (node (ref "U9") (pin "158") (pinfunction "HDMI1_TX0_P_158") (pintype "passive+no_connect"))
    )
    (net (code "165") (name "unconnected-(U9B-HDMI1_TX1_N-Pad154)") (class "Default")
      (node (ref "U9") (pin "154") (pinfunction "HDMI1_TX1_N_154") (pintype "passive+no_connect"))
    )
    (net (code "166") (name "unconnected-(U9B-HDMI1_TX1_P-Pad152)") (class "Default")
      (node (ref "U9") (pin "152") (pinfunction "HDMI1_TX1_P_152") (pintype "passive+no_connect"))
    )
    (net (code "167") (name "unconnected-(U9B-HDMI1_TX2_N-Pad148)") (class "Default")
      (node (ref "U9") (pin "148") (pinfunction "HDMI1_TX2_N_148") (pintype "passive+no_connect"))
    )
    (net (code "168") (name "unconnected-(U9B-HDMI1_TX2_P-Pad146)") (class "Default")
      (node (ref "U9") (pin "146") (pinfunction "HDMI1_TX2_P_146") (pintype "passive+no_connect"))
    )
    (net (code "169") (name "unconnected-(U9B-Reserved-Pad104)") (class "Default")
      (node (ref "U9") (pin "104") (pinfunction "Reserved_104") (pintype "passive+no_connect"))
    )
    (net (code "170") (name "unconnected-(U9B-Reserved-Pad106)") (class "Default")
      (node (ref "U9") (pin "106") (pinfunction "Reserved_106") (pintype "passive+no_connect"))
    )
    (net (code "171") (name "unconnected-(U9B-USB_OTG_ID-Pad101)") (class "Default")
      (node (ref "U9") (pin "101") (pinfunction "USB_OTG_ID_101") (pintype "passive+no_connect"))
    )
    (net (code "172") (name "unconnected-(U9B-VDAC_COMP-Pad111)") (class "Default")
      (node (ref "U9") (pin "111") (pinfunction "VDAC_COMP_111") (pintype "passive+no_connect"))
    )
    (net (code "173") (name "unconnected-(U10-SBU1-PadA8)") (class "Default")
      (node (ref "U10") (pin "A8") (pinfunction "SBU1_A8") (pintype "passive+no_connect"))
    )
    (net (code "174") (name "unconnected-(U10-SBU2-PadB8)") (class "Default")
      (node (ref "U10") (pin "B8") (pinfunction "SBU2_B8") (pintype "passive+no_connect"))
    )
    (net (code "175") (name "unconnected-(U45-RTS#-Pad4)") (class "Default")
      (node (ref "U45") (pin "4") (pinfunction "RTS#_4") (pintype "passive+no_connect"))
    )
  )
)
